# ESP-12_4-relay_board_USB_power.net
KiCad netlist of a schematic drawn in EAGLE
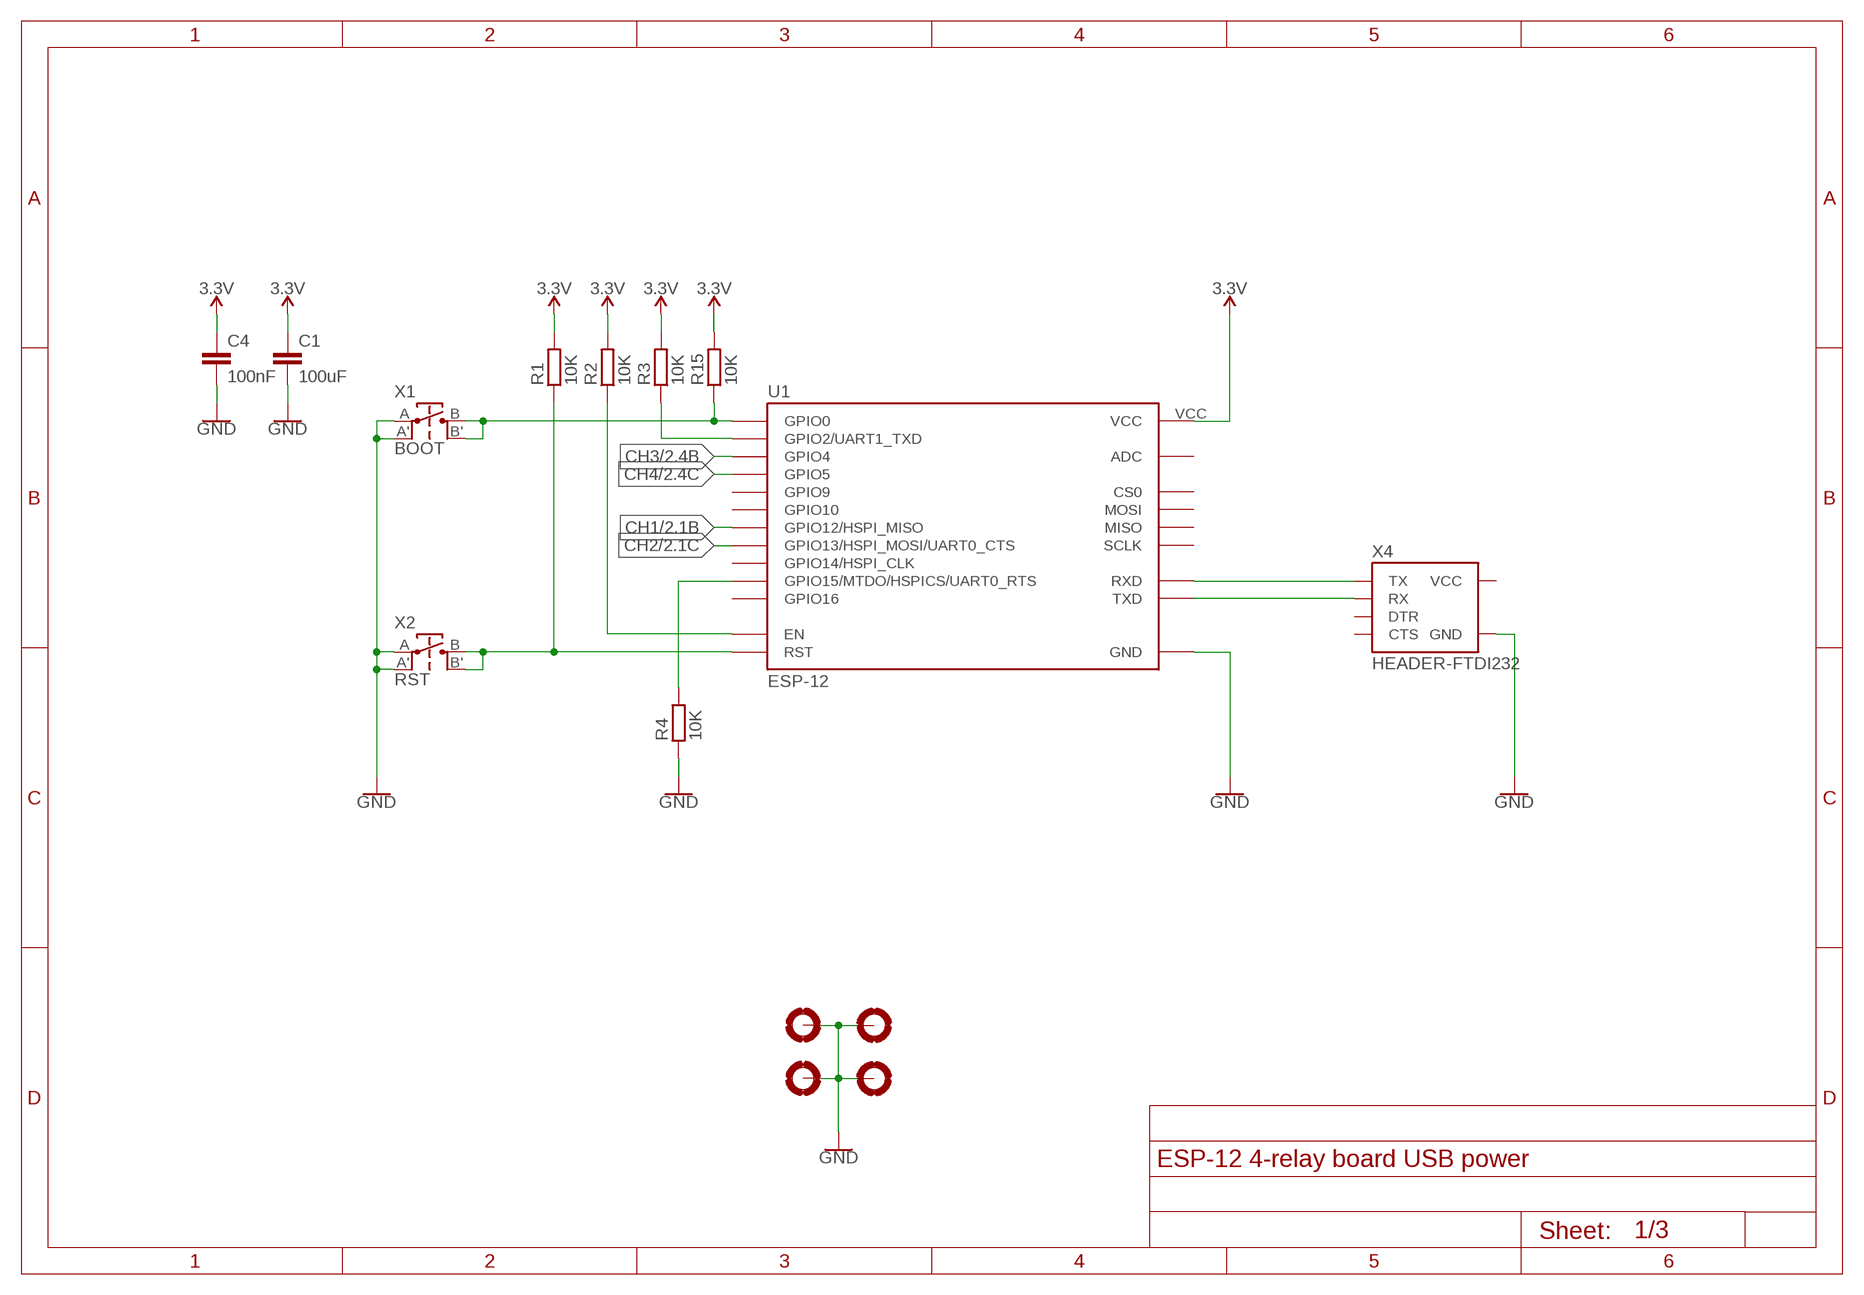
[diagram p0: schematic, sheet 1]
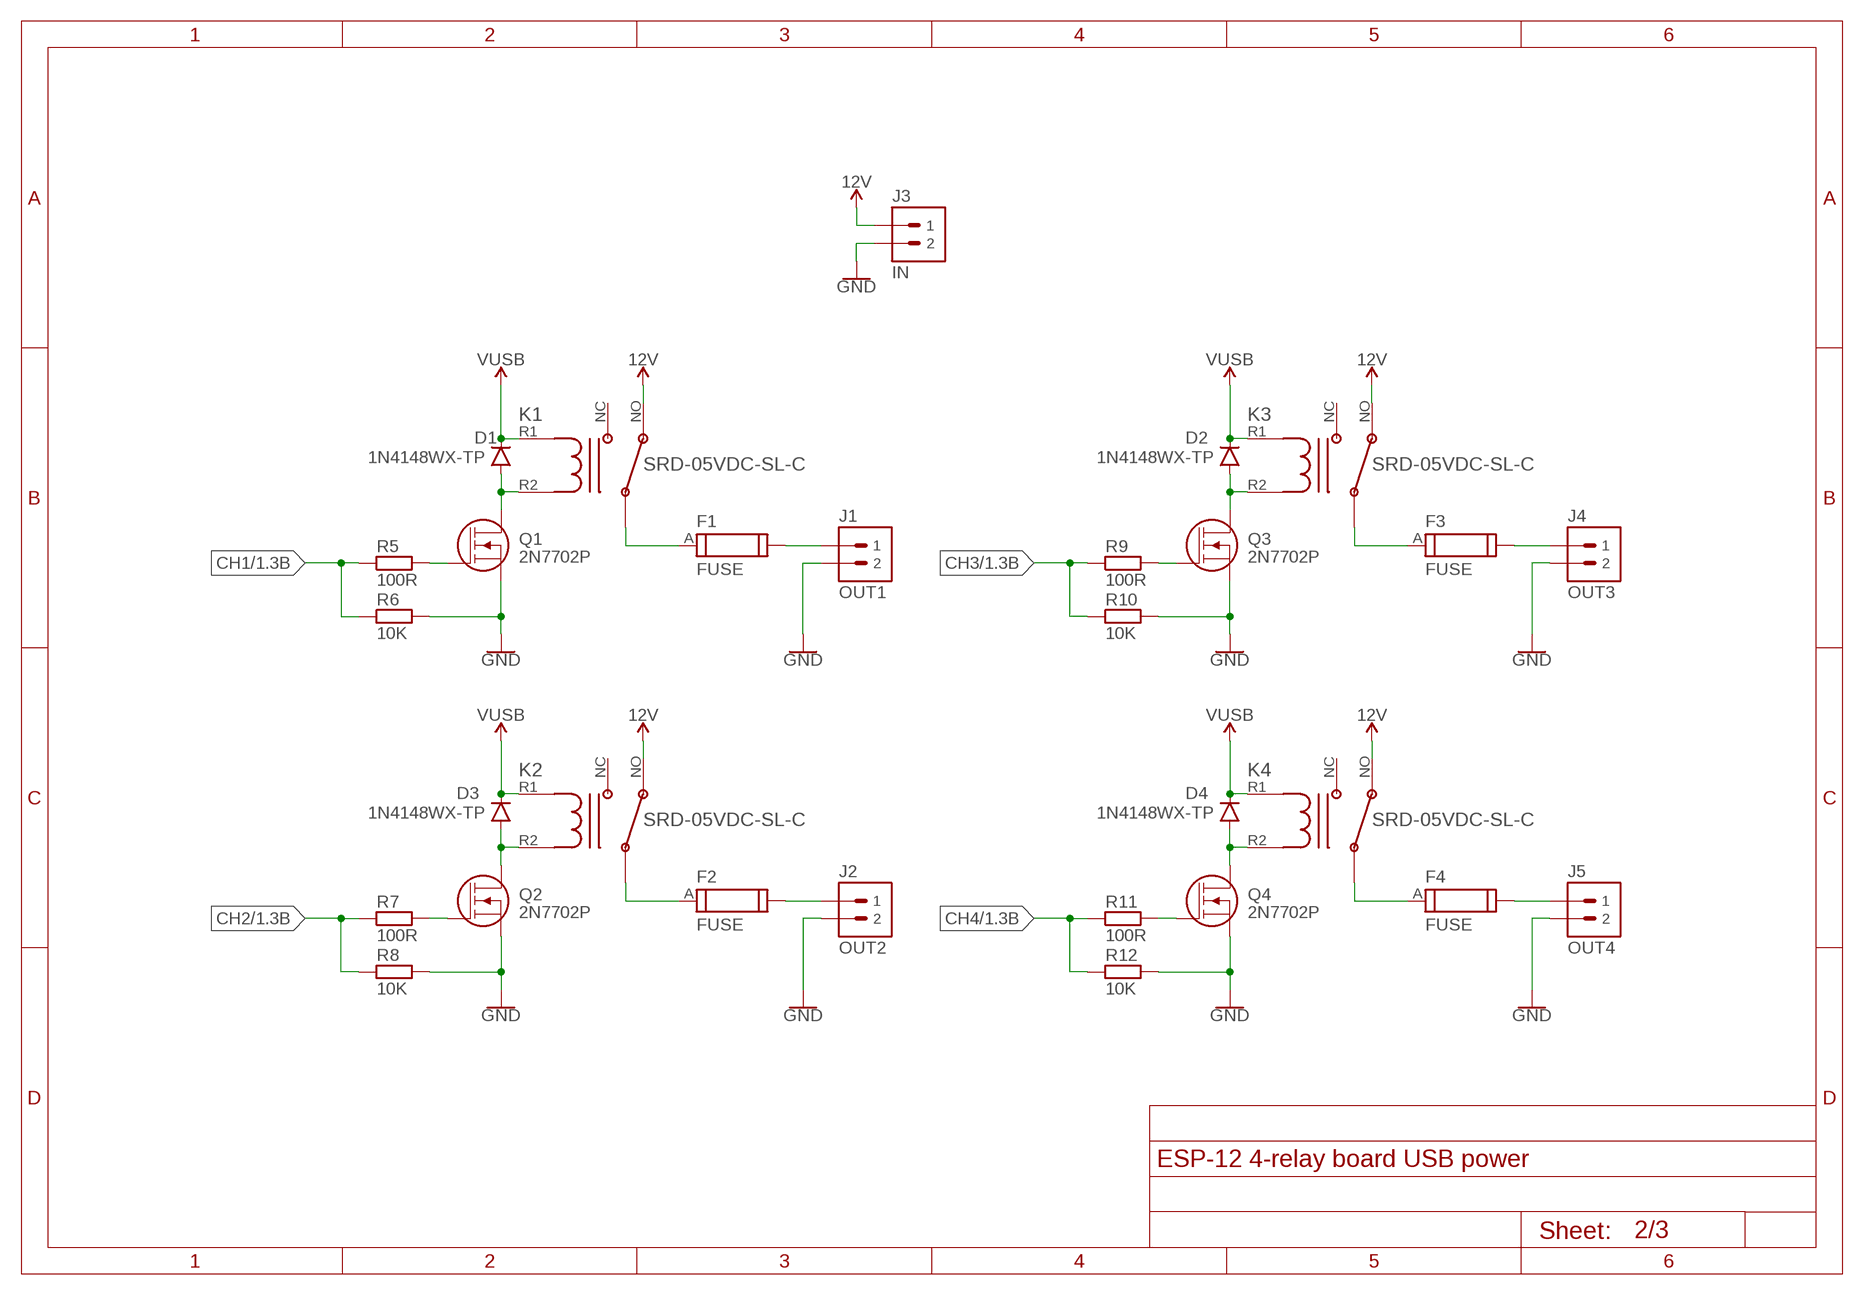
[diagram p1: schematic, sheet 2]
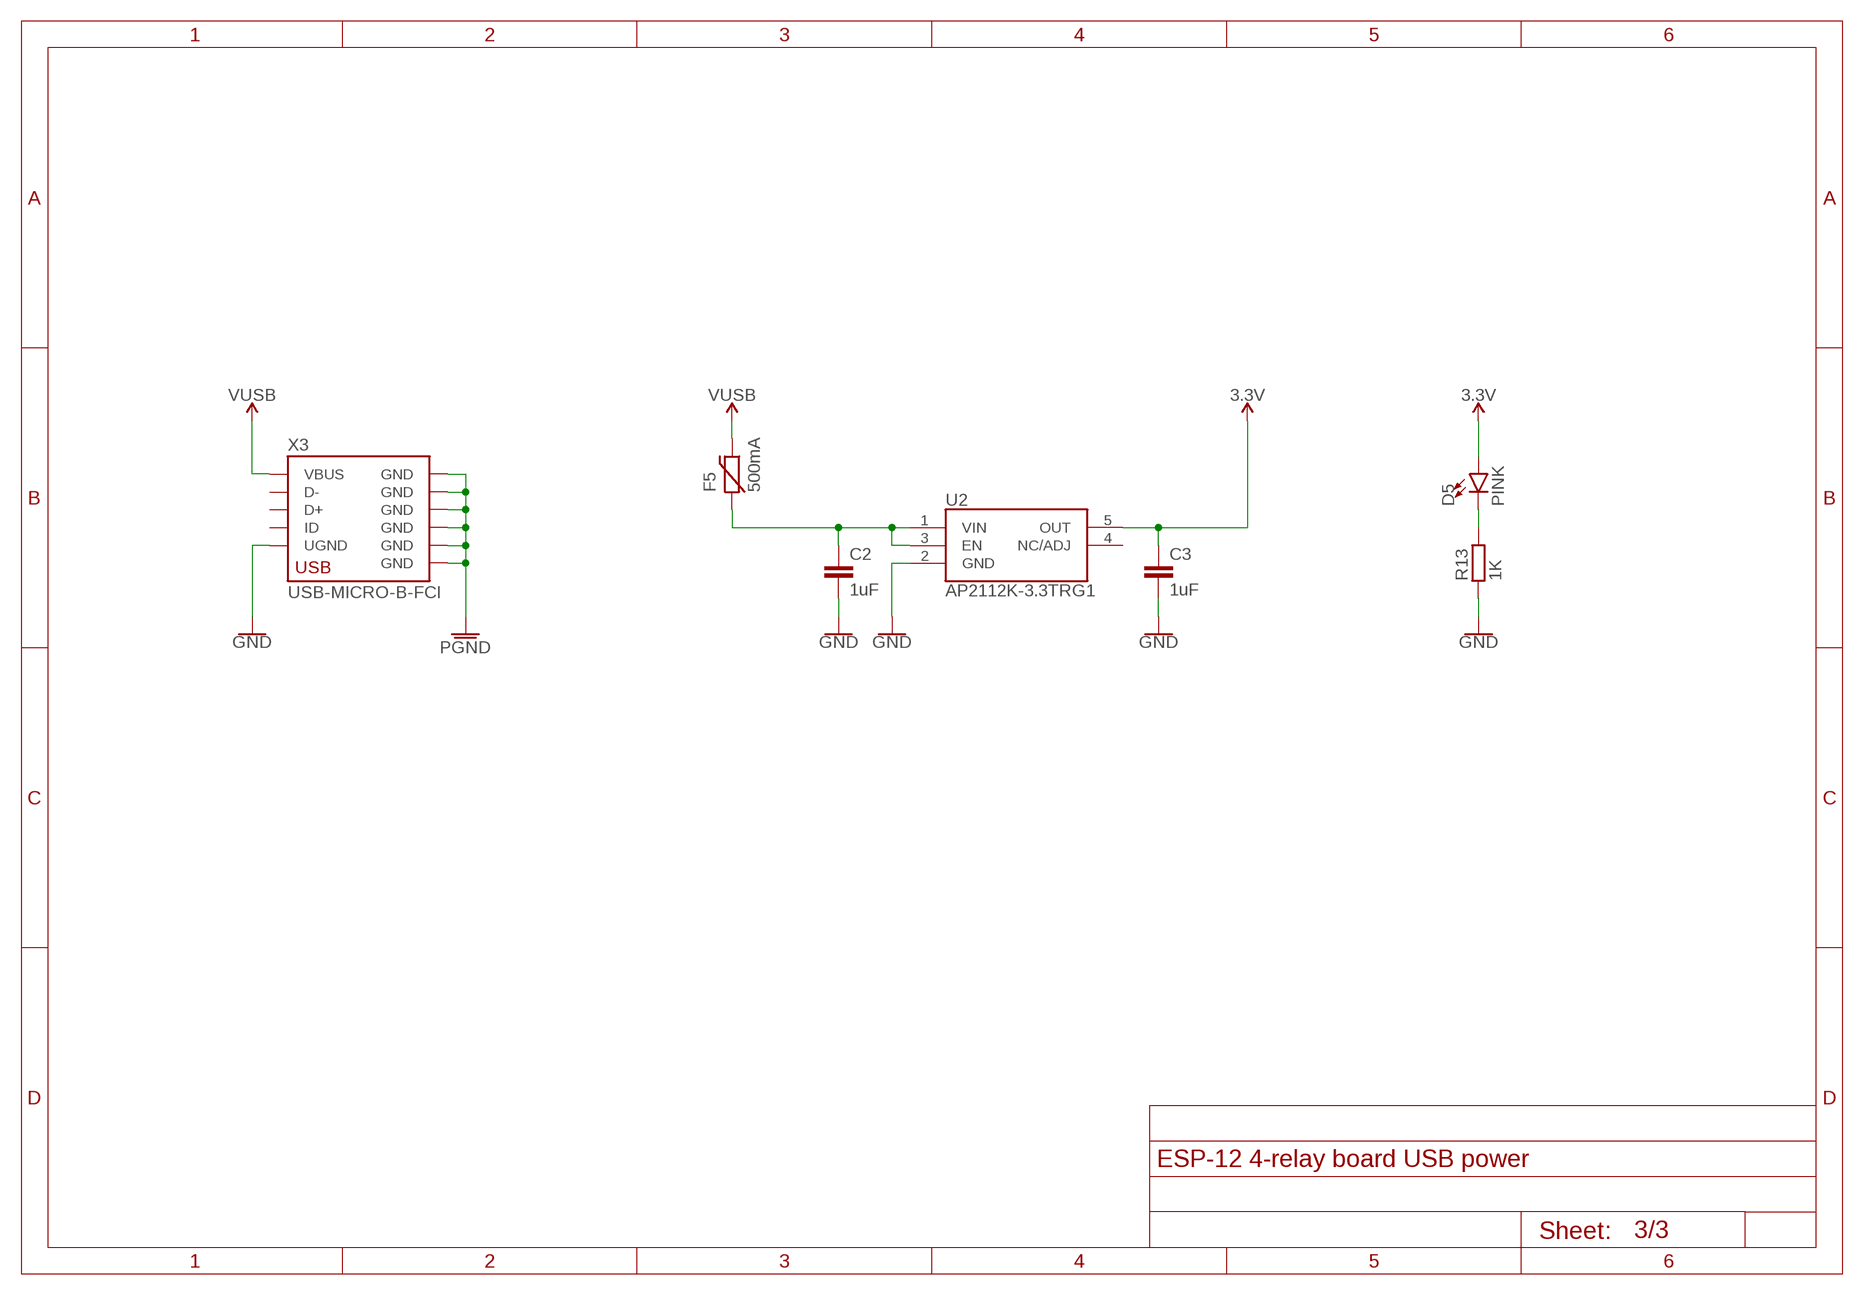
[diagram p2: schematic, sheet 3]

(export (version "E")
  (design (tool "Eeschema 10.0.6"))
  (components
    (comp (ref "C1")
      (value "100uF")
      (footprint "eagle-import:C0603")
      (libsource (lib "eagle-import") (part "CAPC0603"))
    )
    (comp (ref "C4")
      (value "100nF")
      (footprint "eagle-import:C0603")
      (libsource (lib "eagle-import") (part "CAPC0603"))
    )
    (comp (ref "H1")
      (value "MOUNTHOLE-PAD3.2")
      (footprint "eagle-import:3.2-PAD")
      (libsource (lib "eagle-import") (part "MOUNTHOLE-PAD3.2"))
    )
    (comp (ref "H2")
      (value "MOUNTHOLE-PAD3.2")
      (footprint "eagle-import:3.2-PAD")
      (libsource (lib "eagle-import") (part "MOUNTHOLE-PAD3.2"))
    )
    (comp (ref "H3")
      (value "MOUNTHOLE-PAD3.2")
      (footprint "eagle-import:3.2-PAD")
      (libsource (lib "eagle-import") (part "MOUNTHOLE-PAD3.2"))
    )
    (comp (ref "H4")
      (value "MOUNTHOLE-PAD3.2")
      (footprint "eagle-import:3.2-PAD")
      (libsource (lib "eagle-import") (part "MOUNTHOLE-PAD3.2"))
    )
    (comp (ref "R1")
      (value "10K")
      (footprint "eagle-import:R0603")
      (libsource (lib "eagle-import") (part "RESISTOR0603"))
    )
    (comp (ref "R2")
      (value "10K")
      (footprint "eagle-import:R0603")
      (libsource (lib "eagle-import") (part "RESISTOR0603"))
    )
    (comp (ref "R3")
      (value "10K")
      (footprint "eagle-import:R0603")
      (libsource (lib "eagle-import") (part "RESISTOR0603"))
    )
    (comp (ref "R4")
      (value "10K")
      (footprint "eagle-import:R0603")
      (libsource (lib "eagle-import") (part "RESISTOR0603"))
    )
    (comp (ref "R15")
      (value "10K")
      (footprint "eagle-import:R0603")
      (libsource (lib "eagle-import") (part "RESISTOR0603"))
    )
    (comp (ref "U1")
      (value "ESP-12")
      (footprint "eagle-import:ESP-12E")
      (libsource (lib "eagle-import") (part "ESP-12E"))
    )
    (comp (ref "X1")
      (value "BOOT")
      (footprint "eagle-import:TACT-SWITCH-EVQ")
      (libsource (lib "eagle-import") (part "TACT-SWITCHEVQ"))
    )
    (comp (ref "X2")
      (value "RST")
      (footprint "eagle-import:TACT-SWITCH-EVQ")
      (libsource (lib "eagle-import") (part "TACT-SWITCHEVQ"))
    )
    (comp (ref "X4")
      (value "HEADER-FTDI232")
      (footprint "eagle-import:FTDI232-1X06")
      (libsource (lib "eagle-import") (part "HEADER-FTDI232"))
    )
    (comp (ref "C2")
      (value "1uF")
      (footprint "eagle-import:C0603")
      (libsource (lib "eagle-import") (part "CAPC0603"))
    )
    (comp (ref "C3")
      (value "1uF")
      (footprint "eagle-import:C0603")
      (libsource (lib "eagle-import") (part "CAPC0603"))
    )
    (comp (ref "D5")
      (value "PINK")
      (footprint "eagle-import:LED0603")
      (libsource (lib "eagle-import") (part "LED0603"))
    )
    (comp (ref "F5")
      (value "500mA")
      (footprint "eagle-import:PTC-0ZCJ-1206")
      (libsource (lib "eagle-import") (part "PTC0ZCJ"))
    )
    (comp (ref "R13")
      (value "1K")
      (footprint "eagle-import:R0603")
      (libsource (lib "eagle-import") (part "RESISTOR0603"))
    )
    (comp (ref "U2")
      (value "AP2112K-3.3TRG1")
      (footprint "eagle-import:SOT23-5")
      (libsource (lib "eagle-import") (part "REGULATOR-AP2112KK-SOT23-5"))
    )
    (comp (ref "X3")
      (value "USB-MICRO-B-FCI")
      (footprint "eagle-import:USB-MICRO-B-FCI")
      (libsource (lib "eagle-import") (part "USB-MICRO-B-FCI"))
    )
    (comp (ref "D1")
      (value "1N4148WX-TP")
      (footprint "eagle-import:SOD-323")
      (libsource (lib "eagle-import") (part "DIODE1N4148WX-TP"))
    )
    (comp (ref "D2")
      (value "1N4148WX-TP")
      (footprint "eagle-import:SOD-323")
      (libsource (lib "eagle-import") (part "DIODE1N4148WX-TP"))
    )
    (comp (ref "D3")
      (value "1N4148WX-TP")
      (footprint "eagle-import:SOD-323")
      (libsource (lib "eagle-import") (part "DIODE1N4148WX-TP"))
    )
    (comp (ref "D4")
      (value "1N4148WX-TP")
      (footprint "eagle-import:SOD-323")
      (libsource (lib "eagle-import") (part "DIODE1N4148WX-TP"))
    )
    (comp (ref "F1")
      (value "FUSE")
      (footprint "eagle-import:FUSE-TEAL")
      (libsource (lib "eagle-import") (part "FUSETEAL"))
    )
    (comp (ref "F2")
      (value "FUSE")
      (footprint "eagle-import:FUSE-TEAL")
      (libsource (lib "eagle-import") (part "FUSETEAL"))
    )
    (comp (ref "F3")
      (value "FUSE")
      (footprint "eagle-import:FUSE-TEAL")
      (libsource (lib "eagle-import") (part "FUSETEAL"))
    )
    (comp (ref "F4")
      (value "FUSE")
      (footprint "eagle-import:FUSE-TEAL")
      (libsource (lib "eagle-import") (part "FUSETEAL"))
    )
    (comp (ref "J1")
      (value "OUT1")
      (footprint "eagle-import:ONSHORE-OSTTC022162")
      (libsource (lib "eagle-import") (part "TERMINAL-1X02-5.08OSTTC022162"))
    )
    (comp (ref "J2")
      (value "OUT2")
      (footprint "eagle-import:ONSHORE-OSTTC022162")
      (libsource (lib "eagle-import") (part "TERMINAL-1X02-5.08OSTTC022162"))
    )
    (comp (ref "J3")
      (value "IN")
      (footprint "eagle-import:ONSHORE-OSTTC022162")
      (libsource (lib "eagle-import") (part "TERMINAL-1X02-5.08OSTTC022162"))
    )
    (comp (ref "J4")
      (value "OUT3")
      (footprint "eagle-import:ONSHORE-OSTTC022162")
      (libsource (lib "eagle-import") (part "TERMINAL-1X02-5.08OSTTC022162"))
    )
    (comp (ref "J5")
      (value "OUT4")
      (footprint "eagle-import:ONSHORE-OSTTC022162")
      (libsource (lib "eagle-import") (part "TERMINAL-1X02-5.08OSTTC022162"))
    )
    (comp (ref "K1")
      (value "SRD-05VDC-SL-C")
      (footprint "eagle-import:RELAY-SRD-05VDC-SL-C")
      (libsource (lib "eagle-import") (part "RELAYSRD-05VDC-SL-C"))
    )
    (comp (ref "K2")
      (value "SRD-05VDC-SL-C")
      (footprint "eagle-import:RELAY-SRD-05VDC-SL-C")
      (libsource (lib "eagle-import") (part "RELAYSRD-05VDC-SL-C"))
    )
    (comp (ref "K3")
      (value "SRD-05VDC-SL-C")
      (footprint "eagle-import:RELAY-SRD-05VDC-SL-C")
      (libsource (lib "eagle-import") (part "RELAYSRD-05VDC-SL-C"))
    )
    (comp (ref "K4")
      (value "SRD-05VDC-SL-C")
      (footprint "eagle-import:RELAY-SRD-05VDC-SL-C")
      (libsource (lib "eagle-import") (part "RELAYSRD-05VDC-SL-C"))
    )
    (comp (ref "Q1")
      (value "2N7702P")
      (footprint "eagle-import:SOT23-3")
      (libsource (lib "eagle-import") (part "MOSFET-NCHSOT23-3"))
    )
    (comp (ref "Q2")
      (value "2N7702P")
      (footprint "eagle-import:SOT23-3")
      (libsource (lib "eagle-import") (part "MOSFET-NCHSOT23-3"))
    )
    (comp (ref "Q3")
      (value "2N7702P")
      (footprint "eagle-import:SOT23-3")
      (libsource (lib "eagle-import") (part "MOSFET-NCHSOT23-3"))
    )
    (comp (ref "Q4")
      (value "2N7702P")
      (footprint "eagle-import:SOT23-3")
      (libsource (lib "eagle-import") (part "MOSFET-NCHSOT23-3"))
    )
    (comp (ref "R5")
      (value "100R")
      (footprint "eagle-import:R0603")
      (libsource (lib "eagle-import") (part "RESISTOR0603"))
    )
    (comp (ref "R6")
      (value "10K")
      (footprint "eagle-import:R0603")
      (libsource (lib "eagle-import") (part "RESISTOR0603"))
    )
    (comp (ref "R7")
      (value "100R")
      (footprint "eagle-import:R0603")
      (libsource (lib "eagle-import") (part "RESISTOR0603"))
    )
    (comp (ref "R8")
      (value "10K")
      (footprint "eagle-import:R0603")
      (libsource (lib "eagle-import") (part "RESISTOR0603"))
    )
    (comp (ref "R9")
      (value "100R")
      (footprint "eagle-import:R0603")
      (libsource (lib "eagle-import") (part "RESISTOR0603"))
    )
    (comp (ref "R10")
      (value "10K")
      (footprint "eagle-import:R0603")
      (libsource (lib "eagle-import") (part "RESISTOR0603"))
    )
    (comp (ref "R11")
      (value "100R")
      (footprint "eagle-import:R0603")
      (libsource (lib "eagle-import") (part "RESISTOR0603"))
    )
    (comp (ref "R12")
      (value "10K")
      (footprint "eagle-import:R0603")
      (libsource (lib "eagle-import") (part "RESISTOR0603"))
    )
  )
  (nets
    (net (code "1") (name "3.3V") (class "Default")
      (node (ref "C1") (pin "1") (pinfunction "1_1") (pintype "passive"))
      (node (ref "C3") (pin "1") (pinfunction "1_1") (pintype "passive"))
      (node (ref "C4") (pin "1") (pinfunction "1_1") (pintype "passive"))
      (node (ref "D5") (pin "A") (pinfunction "A_A") (pintype "passive"))
      (node (ref "R1") (pin "2") (pinfunction "2_2") (pintype "passive"))
      (node (ref "R15") (pin "2") (pinfunction "2_2") (pintype "passive"))
      (node (ref "R2") (pin "2") (pinfunction "2_2") (pintype "passive"))
      (node (ref "R3") (pin "2") (pinfunction "2_2") (pintype "passive"))
      (node (ref "U1") (pin "VCC") (pinfunction "VCC_VCC") (pintype "bidirectional"))
      (node (ref "U2") (pin "5") (pinfunction "OUT_5") (pintype "power_in"))
    )
    (net (code "2") (name "12V") (class "Default")
      (node (ref "J3") (pin "1") (pinfunction "1_1") (pintype "passive"))
      (node (ref "K1") (pin "NO") (pinfunction "NC_NO") (pintype "bidirectional"))
      (node (ref "K2") (pin "NO") (pinfunction "NC_NO") (pintype "bidirectional"))
      (node (ref "K3") (pin "NO") (pinfunction "NC_NO") (pintype "bidirectional"))
      (node (ref "K4") (pin "NO") (pinfunction "NC_NO") (pintype "bidirectional"))
    )
    (net (code "3") (name "CH1") (class "Default")
      (node (ref "R5") (pin "1") (pinfunction "1_1") (pintype "passive"))
      (node (ref "R6") (pin "1") (pinfunction "1_1") (pintype "passive"))
      (node (ref "U1") (pin "GPIO12") (pinfunction "GPIO12/HSPI_MISO_GPIO12") (pintype "bidirectional"))
    )
    (net (code "4") (name "CH2") (class "Default")
      (node (ref "R7") (pin "1") (pinfunction "1_1") (pintype "passive"))
      (node (ref "R8") (pin "1") (pinfunction "1_1") (pintype "passive"))
      (node (ref "U1") (pin "GPIO13") (pinfunction "GPIO13/HSPI_MOSI/UART0_CTS_GPIO13") (pintype "bidirectional"))
    )
    (net (code "5") (name "CH3") (class "Default")
      (node (ref "R10") (pin "1") (pinfunction "1_1") (pintype "passive"))
      (node (ref "R9") (pin "1") (pinfunction "1_1") (pintype "passive"))
      (node (ref "U1") (pin "GPIO4") (pinfunction "GPIO4_GPIO4") (pintype "bidirectional"))
    )
    (net (code "6") (name "CH4") (class "Default")
      (node (ref "R11") (pin "1") (pinfunction "1_1") (pintype "passive"))
      (node (ref "R12") (pin "1") (pinfunction "1_1") (pintype "passive"))
      (node (ref "U1") (pin "GPIO5") (pinfunction "GPIO5_GPIO5") (pintype "bidirectional"))
    )
    (net (code "7") (name "GND") (class "Default")
      (node (ref "C1") (pin "2") (pinfunction "2_2") (pintype "passive"))
      (node (ref "C2") (pin "2") (pinfunction "2_2") (pintype "passive"))
      (node (ref "C3") (pin "2") (pinfunction "2_2") (pintype "passive"))
      (node (ref "C4") (pin "2") (pinfunction "2_2") (pintype "passive"))
      (node (ref "H1") (pin "B3,2") (pinfunction "MOUNT_B3,2") (pintype "passive"))
      (node (ref "H2") (pin "B3,2") (pinfunction "MOUNT_B3,2") (pintype "passive"))
      (node (ref "H3") (pin "B3,2") (pinfunction "MOUNT_B3,2") (pintype "passive"))
      (node (ref "H4") (pin "B3,2") (pinfunction "MOUNT_B3,2") (pintype "passive"))
      (node (ref "J1") (pin "2") (pinfunction "2_2") (pintype "passive"))
      (node (ref "J2") (pin "2") (pinfunction "2_2") (pintype "passive"))
      (node (ref "J3") (pin "2") (pinfunction "2_2") (pintype "passive"))
      (node (ref "J4") (pin "2") (pinfunction "2_2") (pintype "passive"))
      (node (ref "J5") (pin "2") (pinfunction "2_2") (pintype "passive"))
      (node (ref "Q1") (pin "2") (pinfunction "S_2") (pintype "bidirectional"))
      (node (ref "Q2") (pin "2") (pinfunction "S_2") (pintype "bidirectional"))
      (node (ref "Q3") (pin "2") (pinfunction "S_2") (pintype "bidirectional"))
      (node (ref "Q4") (pin "2") (pinfunction "S_2") (pintype "bidirectional"))
      (node (ref "R10") (pin "2") (pinfunction "2_2") (pintype "passive"))
      (node (ref "R12") (pin "2") (pinfunction "2_2") (pintype "passive"))
      (node (ref "R13") (pin "1") (pinfunction "1_1") (pintype "passive"))
      (node (ref "R4") (pin "1") (pinfunction "1_1") (pintype "passive"))
      (node (ref "R6") (pin "2") (pinfunction "2_2") (pintype "passive"))
      (node (ref "R8") (pin "2") (pinfunction "2_2") (pintype "passive"))
      (node (ref "U1") (pin "GND") (pinfunction "GND_GND") (pintype "bidirectional"))
      (node (ref "U2") (pin "2") (pinfunction "GND_2") (pintype "power_in"))
      (node (ref "X1") (pin "A") (pinfunction "A_A") (pintype "bidirectional"))
      (node (ref "X1") (pin "A'") (pinfunction "A'_A'") (pintype "bidirectional"))
      (node (ref "X2") (pin "A") (pinfunction "A_A") (pintype "bidirectional"))
      (node (ref "X2") (pin "A'") (pinfunction "A'_A'") (pintype "bidirectional"))
      (node (ref "X3") (pin "5") (pinfunction "UGND_5") (pintype "power_in"))
      (node (ref "X4") (pin "GND") (pinfunction "GND_GND") (pintype "power_in"))
    )
    (net (code "8") (name "Net-(D1-A)") (class "Default")
      (node (ref "D1") (pin "2") (pinfunction "A_2") (pintype "passive"))
      (node (ref "K1") (pin "R2") (pinfunction "R2_R2") (pintype "bidirectional"))
      (node (ref "Q1") (pin "3") (pinfunction "D_3") (pintype "bidirectional"))
    )
    (net (code "9") (name "Net-(D2-A)") (class "Default")
      (node (ref "D2") (pin "2") (pinfunction "A_2") (pintype "passive"))
      (node (ref "K3") (pin "R2") (pinfunction "R2_R2") (pintype "bidirectional"))
      (node (ref "Q3") (pin "3") (pinfunction "D_3") (pintype "bidirectional"))
    )
    (net (code "10") (name "Net-(D3-A)") (class "Default")
      (node (ref "D3") (pin "2") (pinfunction "A_2") (pintype "passive"))
      (node (ref "K2") (pin "R2") (pinfunction "R2_R2") (pintype "bidirectional"))
      (node (ref "Q2") (pin "3") (pinfunction "D_3") (pintype "bidirectional"))
    )
    (net (code "11") (name "Net-(D4-A)") (class "Default")
      (node (ref "D4") (pin "2") (pinfunction "A_2") (pintype "passive"))
      (node (ref "K4") (pin "R2") (pinfunction "R2_R2") (pintype "bidirectional"))
      (node (ref "Q4") (pin "3") (pinfunction "D_3") (pintype "bidirectional"))
    )
    (net (code "12") (name "Net-(D5-PadC)") (class "Default")
      (node (ref "D5") (pin "C") (pinfunction "C_C") (pintype "passive"))
      (node (ref "R13") (pin "2") (pinfunction "2_2") (pintype "passive"))
    )
    (net (code "13") (name "Net-(F1-PadA)") (class "Default")
      (node (ref "F1") (pin "A") (pinfunction "A_A") (pintype "bidirectional"))
      (node (ref "K1") (pin "C") (pinfunction "C_C") (pintype "bidirectional"))
    )
    (net (code "14") (name "Net-(F1-PadB)") (class "Default")
      (node (ref "F1") (pin "B") (pinfunction "B_B") (pintype "bidirectional"))
      (node (ref "J1") (pin "1") (pinfunction "1_1") (pintype "passive"))
    )
    (net (code "15") (name "Net-(F2-PadA)") (class "Default")
      (node (ref "F2") (pin "A") (pinfunction "A_A") (pintype "bidirectional"))
      (node (ref "K2") (pin "C") (pinfunction "C_C") (pintype "bidirectional"))
    )
    (net (code "16") (name "Net-(F2-PadB)") (class "Default")
      (node (ref "F2") (pin "B") (pinfunction "B_B") (pintype "bidirectional"))
      (node (ref "J2") (pin "1") (pinfunction "1_1") (pintype "passive"))
    )
    (net (code "17") (name "Net-(F3-PadA)") (class "Default")
      (node (ref "F3") (pin "A") (pinfunction "A_A") (pintype "bidirectional"))
      (node (ref "K3") (pin "C") (pinfunction "C_C") (pintype "bidirectional"))
    )
    (net (code "18") (name "Net-(F3-PadB)") (class "Default")
      (node (ref "F3") (pin "B") (pinfunction "B_B") (pintype "bidirectional"))
      (node (ref "J4") (pin "1") (pinfunction "1_1") (pintype "passive"))
    )
    (net (code "19") (name "Net-(F4-PadA)") (class "Default")
      (node (ref "F4") (pin "A") (pinfunction "A_A") (pintype "bidirectional"))
      (node (ref "K4") (pin "C") (pinfunction "C_C") (pintype "bidirectional"))
    )
    (net (code "20") (name "Net-(F4-PadB)") (class "Default")
      (node (ref "F4") (pin "B") (pinfunction "B_B") (pintype "bidirectional"))
      (node (ref "J5") (pin "1") (pinfunction "1_1") (pintype "passive"))
    )
    (net (code "21") (name "Net-(Q1-G)") (class "Default")
      (node (ref "Q1") (pin "1") (pinfunction "G_1") (pintype "bidirectional"))
      (node (ref "R5") (pin "2") (pinfunction "2_2") (pintype "passive"))
    )
    (net (code "22") (name "Net-(Q2-G)") (class "Default")
      (node (ref "Q2") (pin "1") (pinfunction "G_1") (pintype "bidirectional"))
      (node (ref "R7") (pin "2") (pinfunction "2_2") (pintype "passive"))
    )
    (net (code "23") (name "Net-(Q3-G)") (class "Default")
      (node (ref "Q3") (pin "1") (pinfunction "G_1") (pintype "bidirectional"))
      (node (ref "R9") (pin "2") (pinfunction "2_2") (pintype "passive"))
    )
    (net (code "24") (name "Net-(Q4-G)") (class "Default")
      (node (ref "Q4") (pin "1") (pinfunction "G_1") (pintype "bidirectional"))
      (node (ref "R11") (pin "2") (pinfunction "2_2") (pintype "passive"))
    )
    (net (code "25") (name "Net-(R1-Pad1)") (class "Default")
      (node (ref "R1") (pin "1") (pinfunction "1_1") (pintype "passive"))
      (node (ref "U1") (pin "RST") (pinfunction "RST_RST") (pintype "bidirectional"))
      (node (ref "X2") (pin "B") (pinfunction "B_B") (pintype "bidirectional"))
      (node (ref "X2") (pin "B'") (pinfunction "B'_B'") (pintype "bidirectional"))
    )
    (net (code "26") (name "Net-(R2-Pad1)") (class "Default")
      (node (ref "R2") (pin "1") (pinfunction "1_1") (pintype "passive"))
      (node (ref "U1") (pin "EN") (pinfunction "EN_EN") (pintype "bidirectional"))
    )
    (net (code "27") (name "Net-(R15-Pad1)") (class "Default")
      (node (ref "R15") (pin "1") (pinfunction "1_1") (pintype "passive"))
      (node (ref "U1") (pin "GPIO0") (pinfunction "GPIO0_GPIO0") (pintype "bidirectional"))
      (node (ref "X1") (pin "B") (pinfunction "B_B") (pintype "bidirectional"))
      (node (ref "X1") (pin "B'") (pinfunction "B'_B'") (pintype "bidirectional"))
    )
    (net (code "28") (name "Net-(U1-GPIO2{slash}UART1_TXD)") (class "Default")
      (node (ref "R3") (pin "1") (pinfunction "1_1") (pintype "passive"))
      (node (ref "U1") (pin "GPIO2") (pinfunction "GPIO2/UART1_TXD_GPIO2") (pintype "bidirectional"))
    )
    (net (code "29") (name "Net-(U1-GPIO15{slash}MTDO{slash}HSPICS{slash}UART0_RTS)") (class "Default")
      (node (ref "R4") (pin "2") (pinfunction "2_2") (pintype "passive"))
      (node (ref "U1") (pin "GPIO15") (pinfunction "GPIO15/MTDO/HSPICS/UART0_RTS_GPIO15") (pintype "bidirectional"))
    )
    (net (code "30") (name "Net-(U1-PadRXD)") (class "Default")
      (node (ref "U1") (pin "RXD") (pinfunction "RXD_RXD") (pintype "bidirectional"))
      (node (ref "X4") (pin "TX") (pinfunction "TX_TX") (pintype "output"))
    )
    (net (code "31") (name "Net-(U1-PadTXD)") (class "Default")
      (node (ref "U1") (pin "TXD") (pinfunction "TXD_TXD") (pintype "bidirectional"))
      (node (ref "X4") (pin "RX") (pinfunction "RX_RX") (pintype "input"))
    )
    (net (code "32") (name "Net-(U2-EN)") (class "Default")
      (node (ref "C2") (pin "1") (pinfunction "1_1") (pintype "passive"))
      (node (ref "F5") (pin "1") (pinfunction "1_1") (pintype "bidirectional"))
      (node (ref "U2") (pin "1") (pinfunction "VIN_1") (pintype "power_in"))
      (node (ref "U2") (pin "3") (pinfunction "EN_3") (pintype "input"))
    )
    (net (code "33") (name "PGND") (class "Default")
      (node (ref "X3") (pin "GND@1") (pinfunction "GND_GND@1") (pintype "power_in"))
      (node (ref "X3") (pin "GND@2") (pinfunction "GND_GND@2") (pintype "power_in"))
      (node (ref "X3") (pin "GND@3") (pinfunction "GND_GND@3") (pintype "power_in"))
      (node (ref "X3") (pin "GND@4") (pinfunction "GND_GND@4") (pintype "power_in"))
      (node (ref "X3") (pin "GND@5") (pinfunction "GND_GND@5") (pintype "power_in"))
      (node (ref "X3") (pin "GND@6") (pinfunction "GND_GND@6") (pintype "power_in"))
    )
    (net (code "34") (name "VCC") (class "Default")
      (node (ref "X4") (pin "VCC") (pinfunction "VCC_VCC") (pintype "power_in"))
    )
    (net (code "35") (name "VUSB") (class "Default")
      (node (ref "D1") (pin "1") (pinfunction "C_1") (pintype "passive"))
      (node (ref "D2") (pin "1") (pinfunction "C_1") (pintype "passive"))
      (node (ref "D3") (pin "1") (pinfunction "C_1") (pintype "passive"))
      (node (ref "D4") (pin "1") (pinfunction "C_1") (pintype "passive"))
      (node (ref "F5") (pin "2") (pinfunction "2_2") (pintype "bidirectional"))
      (node (ref "K1") (pin "R1") (pinfunction "R1_R1") (pintype "bidirectional"))
      (node (ref "K2") (pin "R1") (pinfunction "R1_R1") (pintype "bidirectional"))
      (node (ref "K3") (pin "R1") (pinfunction "R1_R1") (pintype "bidirectional"))
      (node (ref "K4") (pin "R1") (pinfunction "R1_R1") (pintype "bidirectional"))
      (node (ref "X3") (pin "1") (pinfunction "VBUS_1") (pintype "power_in"))
    )
    (net (code "36") (name "unconnected-(K1-NO-PadNC)") (class "Default")
      (node (ref "K1") (pin "NC") (pinfunction "NO_NC") (pintype "bidirectional"))
    )
    (net (code "37") (name "unconnected-(K2-NO-PadNC)") (class "Default")
      (node (ref "K2") (pin "NC") (pinfunction "NO_NC") (pintype "bidirectional"))
    )
    (net (code "38") (name "unconnected-(K3-NO-PadNC)") (class "Default")
      (node (ref "K3") (pin "NC") (pinfunction "NO_NC") (pintype "bidirectional"))
    )
    (net (code "39") (name "unconnected-(K4-NO-PadNC)") (class "Default")
      (node (ref "K4") (pin "NC") (pinfunction "NO_NC") (pintype "bidirectional"))
    )
    (net (code "40") (name "unconnected-(U1-GPIO14{slash}HSPI_CLK-PadGPIO14)") (class "Default")
      (node (ref "U1") (pin "GPIO14") (pinfunction "GPIO14/HSPI_CLK_GPIO14") (pintype "bidirectional"))
    )
    (net (code "41") (name "unconnected-(U1-PadADC)") (class "Default")
      (node (ref "U1") (pin "ADC") (pinfunction "ADC_ADC") (pintype "bidirectional"))
    )
    (net (code "42") (name "unconnected-(U1-PadCS0)") (class "Default")
      (node (ref "U1") (pin "CS0") (pinfunction "CS0_CS0") (pintype "bidirectional"))
    )
    (net (code "43") (name "unconnected-(U1-PadGPIO9)") (class "Default")
      (node (ref "U1") (pin "GPIO9") (pinfunction "GPIO9_GPIO9") (pintype "bidirectional"))
    )
    (net (code "44") (name "unconnected-(U1-PadGPIO10)") (class "Default")
      (node (ref "U1") (pin "GPIO10") (pinfunction "GPIO10_GPIO10") (pintype "bidirectional"))
    )
    (net (code "45") (name "unconnected-(U1-PadGPIO16)") (class "Default")
      (node (ref "U1") (pin "GPIO16") (pinfunction "GPIO16_GPIO16") (pintype "bidirectional"))
    )
    (net (code "46") (name "unconnected-(U1-PadMISO)") (class "Default")
      (node (ref "U1") (pin "MISO") (pinfunction "MISO_MISO") (pintype "bidirectional"))
    )
    (net (code "47") (name "unconnected-(U1-PadMOSI)") (class "Default")
      (node (ref "U1") (pin "MOSI") (pinfunction "MOSI_MOSI") (pintype "bidirectional"))
    )
    (net (code "48") (name "unconnected-(U1-PadSCLK)") (class "Default")
      (node (ref "U1") (pin "SCLK") (pinfunction "SCLK_SCLK") (pintype "bidirectional"))
    )
    (net (code "49") (name "unconnected-(U2-NC{slash}ADJ-Pad4)") (class "Default")
      (node (ref "U2") (pin "4") (pinfunction "NC/ADJ_4") (pintype "passive"))
    )
    (net (code "50") (name "unconnected-(X3-D+-Pad3)") (class "Default")
      (node (ref "X3") (pin "3") (pinfunction "D+_3") (pintype "bidirectional"))
    )
    (net (code "51") (name "unconnected-(X3-D--Pad2)") (class "Default")
      (node (ref "X3") (pin "2") (pinfunction "D-_2") (pintype "bidirectional"))
    )
    (net (code "52") (name "unconnected-(X3-ID-Pad4)") (class "Default")
      (node (ref "X3") (pin "4") (pinfunction "ID_4") (pintype "bidirectional"))
    )
    (net (code "53") (name "unconnected-(X4-PadCTS)") (class "Default")
      (node (ref "X4") (pin "CTS") (pinfunction "CTS_CTS") (pintype "output"))
    )
    (net (code "54") (name "unconnected-(X4-PadDTR)") (class "Default")
      (node (ref "X4") (pin "DTR") (pinfunction "DTR_DTR") (pintype "output"))
    )
  )
)
